# Oscillator.net
KiCad netlist of a schematic drawn in Altium Designer
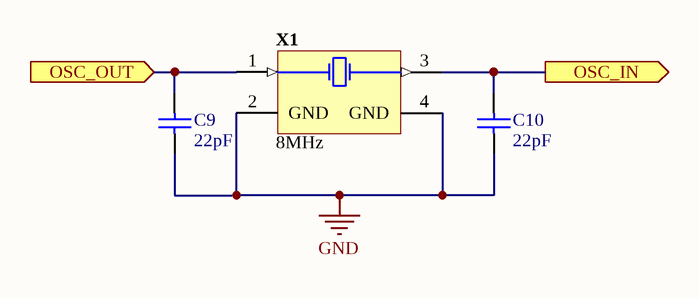
[diagram p0: Oscillator.SchDoc]

(export (version "E")
  (design (tool "Eeschema 10.0.6"))
  (components
    (comp (ref "C9")
      (value "22pF")
      (footprint "CAPC1608X90X35ML10T15")
      (description "Chip Capacitor, 22 pF, +/- 5%, 50 V, -55 to 125 degC, 0603 (1608 Metric), RoHS, Tape and Reel")
      (fields (field (name "MANUFACTURER") "Murata"))
      (libsource (lib "Altium Content Vault") (part "CAP-NP-2"))
    )
    (comp (ref "C10")
      (value "22pF")
      (footprint "CAPC1608X90X35ML10T15")
      (description "Chip Capacitor, 22 pF, +/- 5%, 50 V, -55 to 125 degC, 0603 (1608 Metric), RoHS, Tape and Reel")
      (fields (field (name "MANUFACTURER") "Murata"))
      (libsource (lib "Altium Content Vault") (part "CAP-NP-2"))
    )
    (comp (ref "X1")
      (value "8MHz")
      (footprint "ABRA-ABM3B_V")
      (description "Ceramic SMD Crystal, 8 MHz, +/- 20 ppm, 200 Ohm, -20 to 70 degC, 4-Pin SMD, RoHS, Tape and Reel")
      (libsource (lib "Altium Content Vault") (part "XTAL-1-3-4"))
    )
  )
  (nets
    (net (code "1") (name "/OSC_IN") (class "Default")
      (node (ref "C10") (pin "2") (pinfunction "2_2") (pintype "passive"))
      (node (ref "X1") (pin "3") (pinfunction "X2_3") (pintype "output"))
    )
    (net (code "2") (name "/OSC_OUT") (class "Default")
      (node (ref "C9") (pin "2") (pinfunction "2_2") (pintype "passive"))
      (node (ref "X1") (pin "1") (pinfunction "X1_1") (pintype "input"))
    )
    (net (code "3") (name "GND") (class "Default")
      (node (ref "C10") (pin "1") (pinfunction "1_1") (pintype "passive"))
      (node (ref "C9") (pin "1") (pinfunction "1_1") (pintype "passive"))
      (node (ref "X1") (pin "2") (pinfunction "GND_2") (pintype "power_in"))
      (node (ref "X1") (pin "4") (pinfunction "GND_4") (pintype "power_in"))
    )
  )
)
